# UART.net
KiCad netlist of a schematic drawn in Altium Designer
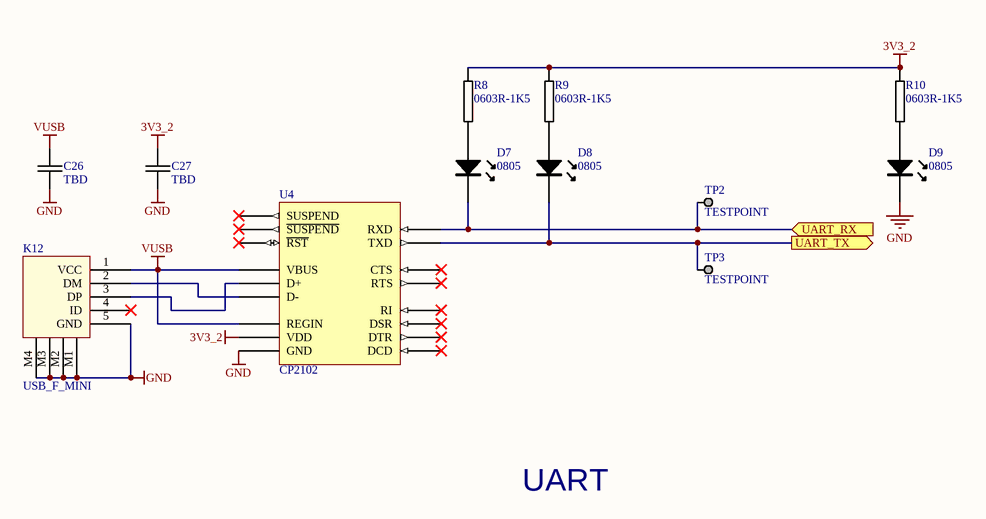
[diagram p0: UART.SchDoc]

(export (version "E")
  (design (tool "Eeschema 10.0.6"))
  (components
    (comp (ref "C26")
      (value "TBD")
      (footprint "1210C-GENERIC")
      (description "CAPACITOR 1210 CERAMIC VALUE TO BE DETERMINED")
      (libsource (lib "RVA_Altium_Library") (part "Passives_Capacitors_1210_1210C-TBD"))
    )
    (comp (ref "C27")
      (value "TBD")
      (footprint "1210C-GENERIC")
      (description "CAPACITOR 1210 CERAMIC VALUE TO BE DETERMINED")
      (libsource (lib "RVA_Altium_Library") (part "Passives_Capacitors_1210_1210C-TBD"))
    )
    (comp (ref "D7")
      (value "0805")
      (footprint "0805LED")
      (libsource (lib "RVA_Altium_Library") (part "0805_LED"))
    )
    (comp (ref "D8")
      (value "0805")
      (footprint "0805LED")
      (libsource (lib "RVA_Altium_Library") (part "0805_LED"))
    )
    (comp (ref "D9")
      (value "0805")
      (footprint "0805LED")
      (libsource (lib "RVA_Altium_Library") (part "0805_LED"))
    )
    (comp (ref "K12")
      (value "USB_F_MINI")
      (footprint "USB_F_MINI")
      (description "MINI USB B FEMALE")
      (libsource (lib "RVA_Altium_Library") (part "USB_F_MINI"))
    )
    (comp (ref "R8")
      (value "0603R-1K5")
      (footprint "0603R-1k5")
      (description "GENERIC RESISTOR 0603")
      (fields (field (name "MANUFACTURER PART NUMBER") "RMCF 1/16 15K 1% R") (field (name "TOLERANCE") "±1%"))
      (libsource (lib "RVA_Altium_Library") (part "0603R-1K5"))
    )
    (comp (ref "R9")
      (value "0603R-1K5")
      (footprint "0603R-1k5")
      (description "GENERIC RESISTOR 0603")
      (fields (field (name "MANUFACTURER PART NUMBER") "RMCF 1/16 15K 1% R") (field (name "TOLERANCE") "±1%"))
      (libsource (lib "RVA_Altium_Library") (part "0603R-1K5"))
    )
    (comp (ref "R10")
      (value "0603R-1K5")
      (footprint "0603R-1k5")
      (description "GENERIC RESISTOR 0603")
      (fields (field (name "MANUFACTURER PART NUMBER") "RMCF 1/16 15K 1% R") (field (name "TOLERANCE") "±1%"))
      (libsource (lib "RVA_Altium_Library") (part "0603R-1K5"))
    )
    (comp (ref "TP2")
      (value "TESTPOINT")
      (footprint "TESTPOINT")
      (description "TESTPOINT SCOPE GRABBER")
      (fields
        (field (name "MANUFACTURER PART NUMBER") "5010")
        (field (name "MANUFACTURER") "Keystone Electronics")
      )
      (libsource (lib "vh_altium_library") (part "TESTPOINT"))
    )
    (comp (ref "TP3")
      (value "TESTPOINT")
      (footprint "TESTPOINT")
      (description "TESTPOINT SCOPE GRABBER")
      (fields
        (field (name "MANUFACTURER PART NUMBER") "5010")
        (field (name "MANUFACTURER") "Keystone Electronics")
      )
      (libsource (lib "vh_altium_library") (part "TESTPOINT"))
    )
    (comp (ref "U4")
      (value "CP2102")
      (footprint "QFN-28")
      (libsource (lib "RVA_Altium_Library") (part "CP2102"))
    )
  )
  (nets
    (net (code "1") (name "/UART_RX") (class "Default")
      (node (ref "D7") (pin "K") (pintype "passive"))
      (node (ref "TP2") (pin "1") (pinfunction "1_1") (pintype "passive"))
      (node (ref "U4") (pin "25") (pinfunction "RXD_25") (pintype "input"))
    )
    (net (code "2") (name "/UART_TX") (class "Default")
      (node (ref "D8") (pin "K") (pintype "passive"))
      (node (ref "TP3") (pin "1") (pinfunction "1_1") (pintype "passive"))
      (node (ref "U4") (pin "26") (pinfunction "TXD_26") (pintype "output"))
    )
    (net (code "3") (name "3V3_2") (class "Default")
      (node (ref "C27") (pin "1") (pintype "passive"))
      (node (ref "R10") (pin "1") (pintype "passive"))
      (node (ref "R8") (pin "1") (pintype "passive"))
      (node (ref "R9") (pin "1") (pintype "passive"))
      (node (ref "U4") (pin "6") (pinfunction "VDD_6") (pintype "power_in"))
    )
    (net (code "4") (name "GND") (class "Default")
      (node (ref "C26") (pin "2") (pintype "passive"))
      (node (ref "C27") (pin "2") (pintype "passive"))
      (node (ref "D9") (pin "K") (pintype "passive"))
      (node (ref "K12") (pin "5") (pinfunction "GND_5") (pintype "passive"))
      (node (ref "K12") (pin "M1") (pinfunction "M1_M1") (pintype "power_in"))
      (node (ref "K12") (pin "M2") (pinfunction "M2_M2") (pintype "power_in"))
      (node (ref "K12") (pin "M3") (pinfunction "M3_M3") (pintype "power_in"))
      (node (ref "K12") (pin "M4") (pinfunction "M4_M4") (pintype "power_in"))
      (node (ref "U4") (pin "3") (pinfunction "GND_3") (pintype "passive"))
    )
    (net (code "5") (name "Net-(D7-PadA)") (class "Default")
      (node (ref "D7") (pin "A") (pintype "passive"))
      (node (ref "R8") (pin "2") (pintype "passive"))
    )
    (net (code "6") (name "Net-(D8-PadA)") (class "Default")
      (node (ref "D8") (pin "A") (pintype "passive"))
      (node (ref "R9") (pin "2") (pintype "passive"))
    )
    (net (code "7") (name "Net-(D9-PadA)") (class "Default")
      (node (ref "D9") (pin "A") (pintype "passive"))
      (node (ref "R10") (pin "2") (pintype "passive"))
    )
    (net (code "8") (name "Net-(K12-DM)") (class "Default")
      (node (ref "K12") (pin "2") (pinfunction "DM_2") (pintype "passive"))
      (node (ref "U4") (pin "5") (pinfunction "D-_5") (pintype "passive"))
    )
    (net (code "9") (name "Net-(K12-DP)") (class "Default")
      (node (ref "K12") (pin "3") (pinfunction "DP_3") (pintype "passive"))
      (node (ref "U4") (pin "4") (pinfunction "D+_4") (pintype "passive"))
    )
    (net (code "10") (name "VUSB") (class "Default")
      (node (ref "C26") (pin "1") (pintype "passive"))
      (node (ref "K12") (pin "1") (pinfunction "VCC_1") (pintype "passive"))
      (node (ref "U4") (pin "7") (pinfunction "REGIN_7") (pintype "passive"))
      (node (ref "U4") (pin "8") (pinfunction "VBUS_8") (pintype "passive"))
    )
    (net (code "11") (name "unconnected-(K12-ID-Pad4)") (class "Default")
      (node (ref "K12") (pin "4") (pinfunction "ID_4") (pintype "passive+no_connect"))
    )
    (net (code "12") (name "unconnected-(U4-CTS-Pad23)") (class "Default")
      (node (ref "U4") (pin "23") (pinfunction "CTS_23") (pintype "input+no_connect"))
    )
    (net (code "13") (name "unconnected-(U4-DCD-Pad1)") (class "Default")
      (node (ref "U4") (pin "1") (pinfunction "DCD_1") (pintype "input+no_connect"))
    )
    (net (code "14") (name "unconnected-(U4-DSR-Pad27)") (class "Default")
      (node (ref "U4") (pin "27") (pinfunction "DSR_27") (pintype "input+no_connect"))
    )
    (net (code "15") (name "unconnected-(U4-DTR-Pad28)") (class "Default")
      (node (ref "U4") (pin "28") (pinfunction "DTR_28") (pintype "output+no_connect"))
    )
    (net (code "16") (name "unconnected-(U4-RI-Pad2)") (class "Default")
      (node (ref "U4") (pin "2") (pinfunction "RI_2") (pintype "input+no_connect"))
    )
    (net (code "17") (name "unconnected-(U4-RTS-Pad24)") (class "Default")
      (node (ref "U4") (pin "24") (pinfunction "RTS_24") (pintype "output+no_connect"))
    )
    (net (code "18") (name "unconnected-(U4-SUSPEND-Pad12)") (class "Default")
      (node (ref "U4") (pin "12") (pinfunction "SUSPEND_12") (pintype "output+no_connect"))
    )
    (net (code "19") (name "unconnected-(U4-~{RST}-Pad9)") (class "Default")
      (node (ref "U4") (pin "9") (pinfunction "~{RST}_9") (pintype "bidirectional+no_connect"))
    )
    (net (code "20") (name "unconnected-(U4-~{SUSPEND}-Pad11)") (class "Default")
      (node (ref "U4") (pin "11") (pinfunction "~{SUSPEND}_11") (pintype "output+no_connect"))
    )
  )
)
